# alfred-core.net
KiCad netlist of a schematic drawn in EAGLE
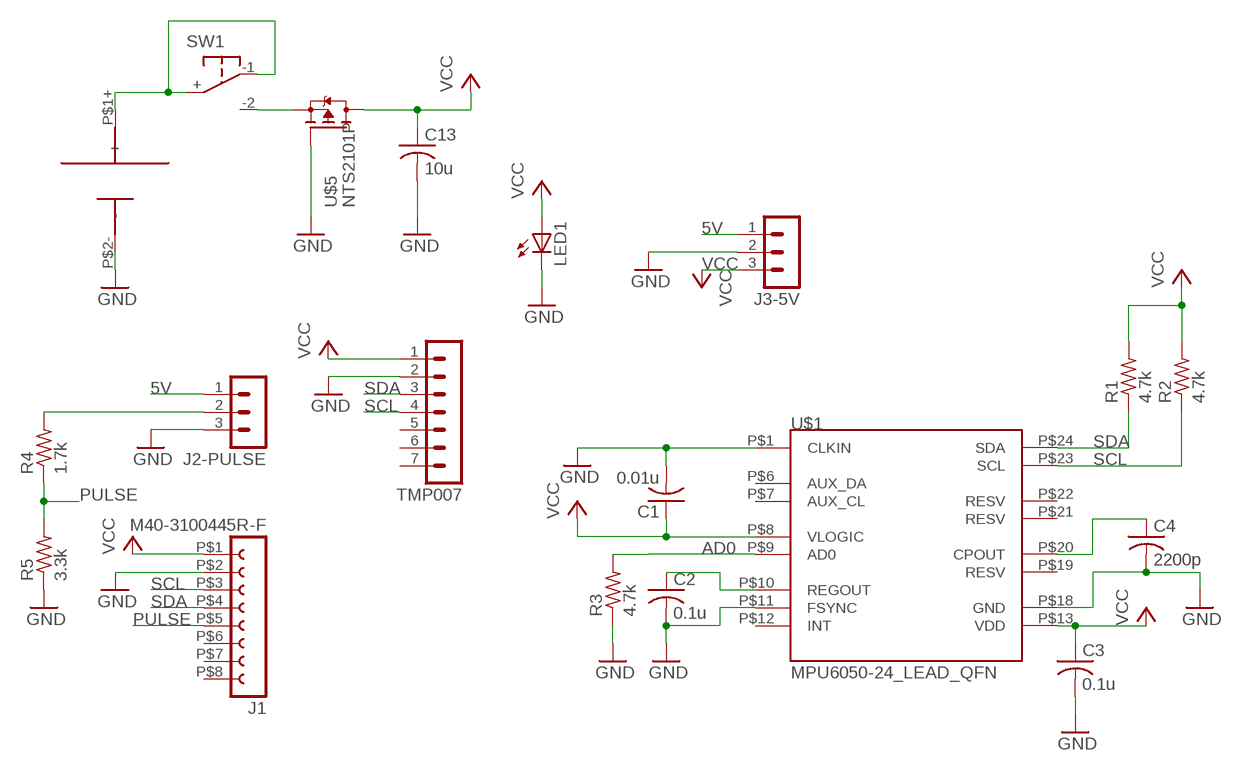
[diagram p0: schematic, sheet 1]

(export (version "E")
  (design (tool "Eeschema 10.0.6"))
  (components
    (comp (ref "BAT1")
      (value "CR2032HOLDER")
      (footprint "eagle-import:CR2032-HOLDER")
      (libsource (lib "eagle-import") (part "CR2032HOLDER"))
    )
    (comp (ref "C1")
      (value "0.01u")
      (footprint "eagle-import:C0603")
      (libsource (lib "eagle-import") (part "C-USC0603"))
    )
    (comp (ref "C2")
      (value "0.1u")
      (footprint "eagle-import:C0603")
      (libsource (lib "eagle-import") (part "C-USC0603"))
    )
    (comp (ref "C3")
      (value "0.1u")
      (footprint "eagle-import:C0603")
      (libsource (lib "eagle-import") (part "C-USC0603"))
    )
    (comp (ref "C4")
      (value "2200p")
      (footprint "eagle-import:C0603")
      (libsource (lib "eagle-import") (part "C-USC0603"))
    )
    (comp (ref "C13")
      (value "10u")
      (footprint "eagle-import:C0603")
      (libsource (lib "eagle-import") (part "C-USC0603"))
    )
    (comp (ref "J1")
      (value "M40-3100445R-F")
      (footprint "eagle-import:8-PO-F")
      (libsource (lib "eagle-import") (part "M40-3100445R-F"))
    )
    (comp (ref "J2-PULSE")
      (value "MA03-1")
      (footprint "eagle-import:MA03-1")
      (libsource (lib "eagle-import") (part "MA03-1"))
    )
    (comp (ref "J3-5V")
      (value "MA03-1")
      (footprint "eagle-import:MA03-1")
      (libsource (lib "eagle-import") (part "MA03-1"))
    )
    (comp (ref "LED1")
      (value "LEDCHIPLED_0603")
      (footprint "eagle-import:CHIPLED_0603")
      (libsource (lib "eagle-import") (part "LEDCHIPLED_0603"))
    )
    (comp (ref "R1")
      (value "4.7k")
      (footprint "eagle-import:R0603")
      (libsource (lib "eagle-import") (part "R-US_R0603"))
    )
    (comp (ref "R2")
      (value "4.7k")
      (footprint "eagle-import:R0603")
      (libsource (lib "eagle-import") (part "R-US_R0603"))
    )
    (comp (ref "R3")
      (value "4.7k")
      (footprint "eagle-import:R0603")
      (libsource (lib "eagle-import") (part "R-US_R0603"))
    )
    (comp (ref "R4")
      (value "1.7k")
      (footprint "eagle-import:R0603")
      (libsource (lib "eagle-import") (part "R-US_R0603"))
    )
    (comp (ref "R5")
      (value "3.3k")
      (footprint "eagle-import:R0603")
      (libsource (lib "eagle-import") (part "R-US_R0603"))
    )
    (comp (ref "SW1")
      (value "JS102011SAQN")
      (footprint "eagle-import:JS102011SAQN")
      (libsource (lib "eagle-import") (part "JS102011SAQN"))
    )
    (comp (ref "TMP007")
      (value "MA07-1")
      (footprint "eagle-import:MA07-1")
      (libsource (lib "eagle-import") (part "MA07-1"))
    )
    (comp (ref "U$1")
      (value "MPU6050-24_LEAD_QFN")
      (footprint "eagle-import:24_LEAD_QFN(4X4X0.9)")
      (libsource (lib "eagle-import") (part "MPU6050-24_LEAD_QFN"))
    )
    (comp (ref "U$5")
      (value "NTS2101P")
      (footprint "eagle-import:SOT323")
      (libsource (lib "eagle-import") (part "NTS2101P"))
    )
  )
  (nets
    (net (code "1") (name "/5V") (class "Default")
      (node (ref "J2-PULSE") (pin "1") (pinfunction "1_1") (pintype "passive"))
      (node (ref "J3-5V") (pin "1") (pinfunction "1_1") (pintype "passive"))
    )
    (net (code "2") (name "/AD0") (class "Default")
      (node (ref "R3") (pin "2") (pinfunction "2_2") (pintype "passive"))
      (node (ref "U$1") (pin "P$9") (pinfunction "AD0_P$9") (pintype "bidirectional"))
    )
    (net (code "3") (name "/PULSE") (class "Default")
      (node (ref "J1") (pin "P$5") (pinfunction "5_P$5") (pintype "passive"))
      (node (ref "R4") (pin "1") (pinfunction "1_1") (pintype "passive"))
      (node (ref "R5") (pin "2") (pinfunction "2_2") (pintype "passive"))
    )
    (net (code "4") (name "/SCL") (class "Default")
      (node (ref "J1") (pin "P$3") (pinfunction "3_P$3") (pintype "passive"))
      (node (ref "R2") (pin "1") (pinfunction "1_1") (pintype "passive"))
      (node (ref "TMP007") (pin "4") (pinfunction "4_4") (pintype "passive"))
      (node (ref "U$1") (pin "P$23") (pinfunction "SCL_P$23") (pintype "bidirectional"))
    )
    (net (code "5") (name "/SDA") (class "Default")
      (node (ref "J1") (pin "P$4") (pinfunction "4_P$4") (pintype "passive"))
      (node (ref "R1") (pin "1") (pinfunction "1_1") (pintype "passive"))
      (node (ref "TMP007") (pin "3") (pinfunction "3_3") (pintype "passive"))
      (node (ref "U$1") (pin "P$24") (pinfunction "SDA_P$24") (pintype "bidirectional"))
    )
    (net (code "6") (name "GND") (class "Default")
      (node (ref "BAT1") (pin "P$2-") (pinfunction "-_P$2-") (pintype "bidirectional"))
      (node (ref "C1") (pin "2") (pinfunction "2_2") (pintype "passive"))
      (node (ref "C13") (pin "2") (pinfunction "2_2") (pintype "passive"))
      (node (ref "C2") (pin "2") (pinfunction "2_2") (pintype "passive"))
      (node (ref "C3") (pin "2") (pinfunction "2_2") (pintype "passive"))
      (node (ref "C4") (pin "2") (pinfunction "2_2") (pintype "passive"))
      (node (ref "J1") (pin "P$2") (pinfunction "2_P$2") (pintype "passive"))
      (node (ref "J2-PULSE") (pin "3") (pinfunction "3_3") (pintype "passive"))
      (node (ref "J3-5V") (pin "2") (pinfunction "2_2") (pintype "passive"))
      (node (ref "LED1") (pin "C") (pinfunction "C_C") (pintype "passive"))
      (node (ref "R3") (pin "1") (pinfunction "1_1") (pintype "passive"))
      (node (ref "R5") (pin "1") (pinfunction "1_1") (pintype "passive"))
      (node (ref "TMP007") (pin "2") (pinfunction "2_2") (pintype "passive"))
      (node (ref "U$1") (pin "P$1") (pinfunction "CLKIN_P$1") (pintype "input"))
      (node (ref "U$1") (pin "P$11") (pinfunction "FSYNC_P$11") (pintype "bidirectional"))
      (node (ref "U$1") (pin "P$18") (pinfunction "GND_P$18") (pintype "power_in"))
      (node (ref "U$5") (pin "G") (pinfunction "G_G") (pintype "passive"))
    )
    (net (code "7") (name "Net-(BAT1-+)") (class "Default")
      (node (ref "BAT1") (pin "P$1+") (pinfunction "+_P$1+") (pintype "bidirectional"))
      (node (ref "SW1") (pin "+") (pinfunction "P$2_+") (pintype "bidirectional"))
      (node (ref "SW1") (pin "-1") (pinfunction "P$1_-1") (pintype "bidirectional"))
    )
    (net (code "8") (name "Net-(J2-PULSE-Pad2)") (class "Default")
      (node (ref "J2-PULSE") (pin "2") (pinfunction "2_2") (pintype "passive"))
      (node (ref "R4") (pin "2") (pinfunction "2_2") (pintype "passive"))
    )
    (net (code "9") (name "Net-(SW1-P$3)") (class "Default")
      (node (ref "SW1") (pin "-2") (pinfunction "P$3_-2") (pintype "bidirectional"))
      (node (ref "U$5") (pin "S") (pinfunction "S_S") (pintype "passive"))
    )
    (net (code "10") (name "Net-(U$1-CPOUT)") (class "Default")
      (node (ref "C4") (pin "1") (pinfunction "1_1") (pintype "passive"))
      (node (ref "U$1") (pin "P$20") (pinfunction "CPOUT_P$20") (pintype "bidirectional"))
    )
    (net (code "11") (name "Net-(U$1-REGOUT)") (class "Default")
      (node (ref "C2") (pin "1") (pinfunction "1_1") (pintype "passive"))
      (node (ref "U$1") (pin "P$10") (pinfunction "REGOUT_P$10") (pintype "bidirectional"))
    )
    (net (code "12") (name "VCC") (class "Default")
      (node (ref "C1") (pin "1") (pinfunction "1_1") (pintype "passive"))
      (node (ref "C13") (pin "1") (pinfunction "1_1") (pintype "passive"))
      (node (ref "C3") (pin "1") (pinfunction "1_1") (pintype "passive"))
      (node (ref "J1") (pin "P$1") (pinfunction "1_P$1") (pintype "passive"))
      (node (ref "J3-5V") (pin "3") (pinfunction "3_3") (pintype "passive"))
      (node (ref "LED1") (pin "A") (pinfunction "A_A") (pintype "passive"))
      (node (ref "R1") (pin "2") (pinfunction "2_2") (pintype "passive"))
      (node (ref "R2") (pin "2") (pinfunction "2_2") (pintype "passive"))
      (node (ref "TMP007") (pin "1") (pinfunction "1_1") (pintype "passive"))
      (node (ref "U$1") (pin "P$13") (pinfunction "VDD_P$13") (pintype "power_in"))
      (node (ref "U$1") (pin "P$8") (pinfunction "VLOGIC_P$8") (pintype "bidirectional"))
      (node (ref "U$5") (pin "D") (pinfunction "D_D") (pintype "passive"))
    )
    (net (code "13") (name "unconnected-(J1-6-PadP$6)") (class "Default")
      (node (ref "J1") (pin "P$6") (pinfunction "6_P$6") (pintype "passive"))
    )
    (net (code "14") (name "unconnected-(J1-7-PadP$7)") (class "Default")
      (node (ref "J1") (pin "P$7") (pinfunction "7_P$7") (pintype "passive"))
    )
    (net (code "15") (name "unconnected-(J1-8-PadP$8)") (class "Default")
      (node (ref "J1") (pin "P$8") (pinfunction "8_P$8") (pintype "passive"))
    )
    (net (code "16") (name "unconnected-(TMP007-Pad5)") (class "Default")
      (node (ref "TMP007") (pin "5") (pinfunction "5_5") (pintype "passive"))
    )
    (net (code "17") (name "unconnected-(TMP007-Pad6)") (class "Default")
      (node (ref "TMP007") (pin "6") (pinfunction "6_6") (pintype "passive"))
    )
    (net (code "18") (name "unconnected-(TMP007-Pad7)") (class "Default")
      (node (ref "TMP007") (pin "7") (pinfunction "7_7") (pintype "passive"))
    )
    (net (code "19") (name "unconnected-(U$1-AUX_CL-PadP$7)") (class "Default")
      (node (ref "U$1") (pin "P$7") (pinfunction "AUX_CL_P$7") (pintype "bidirectional"))
    )
    (net (code "20") (name "unconnected-(U$1-AUX_DA-PadP$6)") (class "Default")
      (node (ref "U$1") (pin "P$6") (pinfunction "AUX_DA_P$6") (pintype "bidirectional"))
    )
    (net (code "21") (name "unconnected-(U$1-INT-PadP$12)") (class "Default")
      (node (ref "U$1") (pin "P$12") (pinfunction "INT_P$12") (pintype "bidirectional"))
    )
    (net (code "22") (name "unconnected-(U$1-RESV-PadP$19)") (class "Default")
      (node (ref "U$1") (pin "P$19") (pinfunction "RESV_P$19") (pintype "bidirectional"))
    )
    (net (code "23") (name "unconnected-(U$1-RESV-PadP$21)") (class "Default")
      (node (ref "U$1") (pin "P$21") (pinfunction "RESV_P$21") (pintype "bidirectional"))
    )
    (net (code "24") (name "unconnected-(U$1-RESV-PadP$22)") (class "Default")
      (node (ref "U$1") (pin "P$22") (pinfunction "RESV_P$22") (pintype "output"))
    )
  )
)
